# MEGA328.net
KiCad netlist of a schematic drawn in EAGLE
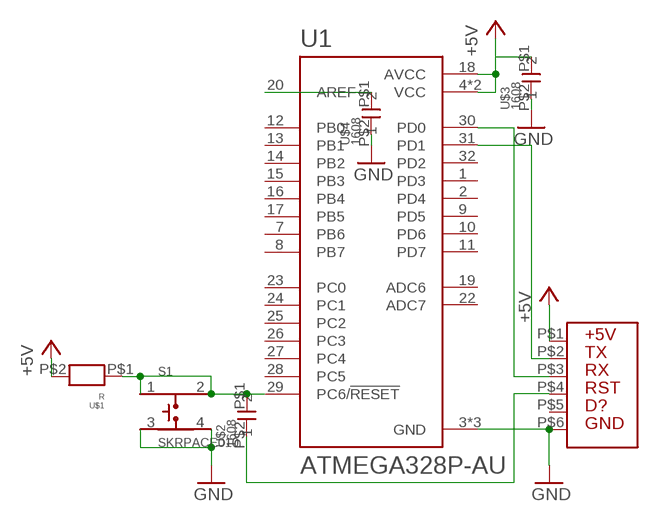
[diagram p0: schematic, sheet 1]

(export (version "E")
  (design (tool "Eeschema 10.0.6"))
  (components
    (comp (ref "S1")
      (value "SKRPACE010")
      (footprint "eagle-import:SW_SKRPACE010")
      (fields (field (name "MF") "ALPS"))
      (libsource (lib "eagle-import") (part "SKRPACE010"))
    )
    (comp (ref "U$1") (value "R") (footprint "eagle-import:1608") (libsource (lib "eagle-import") (part "R")))
    (comp (ref "U$2")
      (value "1608")
      (footprint "eagle-import:CON")
      (libsource (lib "eagle-import") (part "1608"))
    )
    (comp (ref "U$3")
      (value "1608")
      (footprint "eagle-import:CON")
      (libsource (lib "eagle-import") (part "1608"))
    )
    (comp (ref "U$4")
      (value "1608")
      (footprint "eagle-import:CON")
      (libsource (lib "eagle-import") (part "1608"))
    )
    (comp (ref "U$5") (value "SI") (footprint "eagle-import:SI") (libsource (lib "eagle-import") (part "SI")))
    (comp (ref "U1")
      (value "ATMEGA328P-AU")
      (footprint "eagle-import:QFP80P900X900X120-32N")
      (fields (field (name "MF") "Microchip Technology"))
      (libsource (lib "eagle-import") (part "ATMEGA328P-AU"))
    )
  )
  (nets
    (net (code "1") (name "+5V") (class "Default")
      (node (ref "U$1") (pin "P$2") (pinfunction "P$2_P$2") (pintype "bidirectional"))
      (node (ref "U$3") (pin "P$1") (pinfunction "1_P$1") (pintype "bidirectional"))
      (node (ref "U$5") (pin "P$1") (pinfunction "P$1_P$1") (pintype "bidirectional"))
      (node (ref "U1") (pin "18") (pinfunction "AVCC_18") (pintype "power_in"))
      (node (ref "U1") (pin "4") (pinfunction "VCC_4") (pintype "power_in"))
      (node (ref "U1") (pin "6") (pinfunction "VCC_6") (pintype "power_in"))
    )
    (net (code "2") (name "GND") (class "Default")
      (node (ref "S1") (pin "3") (pinfunction "3_3") (pintype "bidirectional"))
      (node (ref "S1") (pin "4") (pinfunction "4_4") (pintype "bidirectional"))
      (node (ref "U$3") (pin "P$2") (pinfunction "2_P$2") (pintype "bidirectional"))
      (node (ref "U$4") (pin "P$2") (pinfunction "2_P$2") (pintype "bidirectional"))
      (node (ref "U$5") (pin "P$6") (pinfunction "P$6_P$6") (pintype "bidirectional"))
      (node (ref "U1") (pin "21") (pinfunction "GND_21") (pintype "power_in"))
      (node (ref "U1") (pin "3") (pinfunction "GND_3") (pintype "power_in"))
      (node (ref "U1") (pin "5") (pinfunction "GND_5") (pintype "power_in"))
    )
    (net (code "3") (name "Net-(U$2-1)") (class "Default")
      (node (ref "S1") (pin "1") (pinfunction "1_1") (pintype "bidirectional"))
      (node (ref "S1") (pin "2") (pinfunction "2_2") (pintype "bidirectional"))
      (node (ref "U$1") (pin "P$1") (pinfunction "P$1_P$1") (pintype "bidirectional"))
      (node (ref "U$2") (pin "P$1") (pinfunction "1_P$1") (pintype "bidirectional"))
      (node (ref "U1") (pin "29") (pinfunction "PC6/~{RESET}_29") (pintype "bidirectional"))
    )
    (net (code "4") (name "Net-(U$2-2)") (class "Default")
      (node (ref "U$2") (pin "P$2") (pinfunction "2_P$2") (pintype "bidirectional"))
      (node (ref "U$5") (pin "P$4") (pinfunction "P$4_P$4") (pintype "bidirectional"))
    )
    (net (code "5") (name "Net-(U$4-1)") (class "Default")
      (node (ref "U$4") (pin "P$1") (pinfunction "1_P$1") (pintype "bidirectional"))
      (node (ref "U1") (pin "20") (pinfunction "AREF_20") (pintype "input"))
    )
    (net (code "6") (name "Net-(U1-PD0)") (class "Default")
      (node (ref "U$5") (pin "P$3") (pinfunction "P$3_P$3") (pintype "bidirectional"))
      (node (ref "U1") (pin "30") (pinfunction "PD0_30") (pintype "bidirectional"))
    )
    (net (code "7") (name "Net-(U1-PD1)") (class "Default")
      (node (ref "U$5") (pin "P$2") (pinfunction "P$2_P$2") (pintype "bidirectional"))
      (node (ref "U1") (pin "31") (pinfunction "PD1_31") (pintype "bidirectional"))
    )
    (net (code "8") (name "unconnected-(U$5-PadP$5)") (class "Default")
      (node (ref "U$5") (pin "P$5") (pinfunction "P$5_P$5") (pintype "bidirectional"))
    )
    (net (code "9") (name "unconnected-(U1-ADC6-Pad19)") (class "Default")
      (node (ref "U1") (pin "19") (pinfunction "ADC6_19") (pintype "bidirectional"))
    )
    (net (code "10") (name "unconnected-(U1-ADC7-Pad22)") (class "Default")
      (node (ref "U1") (pin "22") (pinfunction "ADC7_22") (pintype "bidirectional"))
    )
    (net (code "11") (name "unconnected-(U1-PB0-Pad12)") (class "Default")
      (node (ref "U1") (pin "12") (pinfunction "PB0_12") (pintype "bidirectional"))
    )
    (net (code "12") (name "unconnected-(U1-PB1-Pad13)") (class "Default")
      (node (ref "U1") (pin "13") (pinfunction "PB1_13") (pintype "bidirectional"))
    )
    (net (code "13") (name "unconnected-(U1-PB2-Pad14)") (class "Default")
      (node (ref "U1") (pin "14") (pinfunction "PB2_14") (pintype "bidirectional"))
    )
    (net (code "14") (name "unconnected-(U1-PB3-Pad15)") (class "Default")
      (node (ref "U1") (pin "15") (pinfunction "PB3_15") (pintype "bidirectional"))
    )
    (net (code "15") (name "unconnected-(U1-PB4-Pad16)") (class "Default")
      (node (ref "U1") (pin "16") (pinfunction "PB4_16") (pintype "bidirectional"))
    )
    (net (code "16") (name "unconnected-(U1-PB5-Pad17)") (class "Default")
      (node (ref "U1") (pin "17") (pinfunction "PB5_17") (pintype "bidirectional"))
    )
    (net (code "17") (name "unconnected-(U1-PB6-Pad7)") (class "Default")
      (node (ref "U1") (pin "7") (pinfunction "PB6_7") (pintype "bidirectional"))
    )
    (net (code "18") (name "unconnected-(U1-PB7-Pad8)") (class "Default")
      (node (ref "U1") (pin "8") (pinfunction "PB7_8") (pintype "bidirectional"))
    )
    (net (code "19") (name "unconnected-(U1-PC0-Pad23)") (class "Default")
      (node (ref "U1") (pin "23") (pinfunction "PC0_23") (pintype "bidirectional"))
    )
    (net (code "20") (name "unconnected-(U1-PC1-Pad24)") (class "Default")
      (node (ref "U1") (pin "24") (pinfunction "PC1_24") (pintype "bidirectional"))
    )
    (net (code "21") (name "unconnected-(U1-PC2-Pad25)") (class "Default")
      (node (ref "U1") (pin "25") (pinfunction "PC2_25") (pintype "bidirectional"))
    )
    (net (code "22") (name "unconnected-(U1-PC3-Pad26)") (class "Default")
      (node (ref "U1") (pin "26") (pinfunction "PC3_26") (pintype "bidirectional"))
    )
    (net (code "23") (name "unconnected-(U1-PC4-Pad27)") (class "Default")
      (node (ref "U1") (pin "27") (pinfunction "PC4_27") (pintype "bidirectional"))
    )
    (net (code "24") (name "unconnected-(U1-PC5-Pad28)") (class "Default")
      (node (ref "U1") (pin "28") (pinfunction "PC5_28") (pintype "bidirectional"))
    )
    (net (code "25") (name "unconnected-(U1-PD2-Pad32)") (class "Default")
      (node (ref "U1") (pin "32") (pinfunction "PD2_32") (pintype "bidirectional"))
    )
    (net (code "26") (name "unconnected-(U1-PD3-Pad1)") (class "Default")
      (node (ref "U1") (pin "1") (pinfunction "PD3_1") (pintype "bidirectional"))
    )
    (net (code "27") (name "unconnected-(U1-PD4-Pad2)") (class "Default")
      (node (ref "U1") (pin "2") (pinfunction "PD4_2") (pintype "bidirectional"))
    )
    (net (code "28") (name "unconnected-(U1-PD5-Pad9)") (class "Default")
      (node (ref "U1") (pin "9") (pinfunction "PD5_9") (pintype "bidirectional"))
    )
    (net (code "29") (name "unconnected-(U1-PD6-Pad10)") (class "Default")
      (node (ref "U1") (pin "10") (pinfunction "PD6_10") (pintype "bidirectional"))
    )
    (net (code "30") (name "unconnected-(U1-PD7-Pad11)") (class "Default")
      (node (ref "U1") (pin "11") (pinfunction "PD7_11") (pintype "bidirectional"))
    )
  )
)
